# ESP8266_MySensorsGateway_v1_3.net
KiCad netlist of a schematic drawn in EAGLE
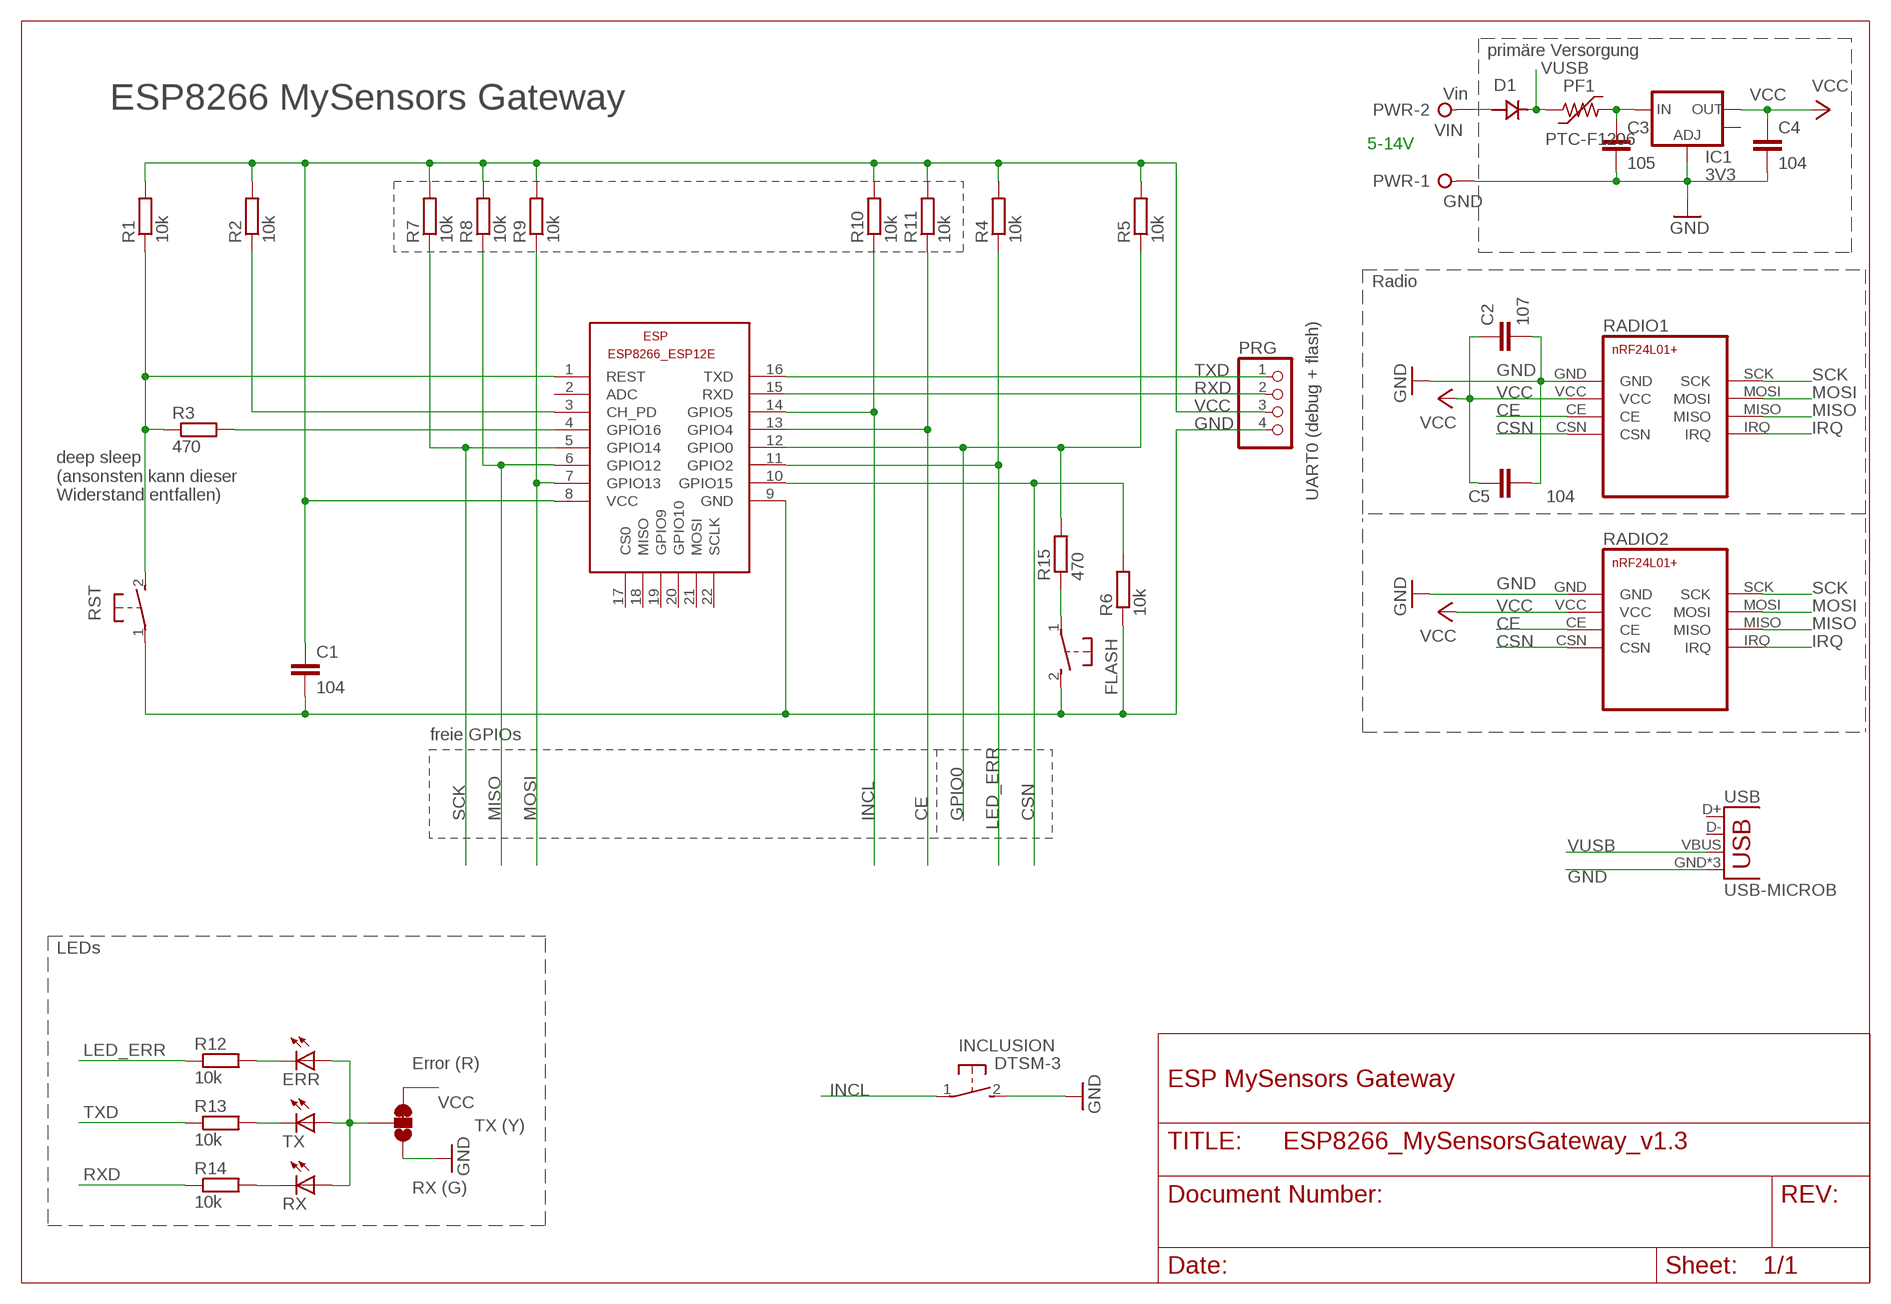
[diagram p0: schematic, sheet 1]

(export (version "E")
  (design (tool "Eeschema 10.0.6"))
  (components
    (comp (ref "C1")
      (value "104")
      (footprint "eagle-import:C0805")
      (libsource (lib "eagle-import") (part "C-EUC0805"))
    )
    (comp (ref "C2")
      (value "107")
      (footprint "eagle-import:MY1210")
      (libsource (lib "eagle-import") (part "C"))
    )
    (comp (ref "C3")
      (value "105")
      (footprint "eagle-import:C0805")
      (libsource (lib "eagle-import") (part "C-EUC0805"))
    )
    (comp (ref "C4")
      (value "104")
      (footprint "eagle-import:C0805")
      (libsource (lib "eagle-import") (part "C-EUC0805"))
    )
    (comp (ref "C5")
      (value "104")
      (footprint "eagle-import:C0805")
      (libsource (lib "eagle-import") (part "C-EUC0805"))
    )
    (comp (ref "D1")
      (value "SS14")
      (footprint "eagle-import:DO214")
      (libsource (lib "eagle-import") (part "SS14"))
    )
    (comp (ref "ERR")
      (value "R")
      (footprint "eagle-import:CHIPLED_1206")
      (libsource (lib "eagle-import") (part "LEDCHIPLED_1206"))
    )
    (comp (ref "ESP")
      (value "µC")
      (footprint "eagle-import:ESP8266-ESP12E")
      (libsource (lib "eagle-import") (part "ESP8266-12EESP8266-ESP12E"))
    )
    (comp (ref "FLASH")
      (value "DTSM-3")
      (footprint "eagle-import:DTSM-3")
      (libsource (lib "eagle-import") (part "DTSM-3"))
    )
    (comp (ref "IC1")
      (value "3V3")
      (footprint "eagle-import:SOT223")
      (libsource (lib "eagle-import") (part "V_REG_LM1117SOT223"))
    )
    (comp (ref "INCLUSION")
      (value "DTSM-3")
      (footprint "eagle-import:DTSM-3")
      (libsource (lib "eagle-import") (part "DTSM-3"))
    )
    (comp (ref "PF1")
      (value "PTC-F1206")
      (footprint "eagle-import:F1206")
      (libsource (lib "eagle-import") (part "PTC-F1206"))
    )
    (comp (ref "PRG")
      (value "PINHD-1X4_S")
      (footprint "eagle-import:1X04")
      (libsource (lib "eagle-import") (part "PINHD-1X4_S"))
    )
    (comp (ref "PWR")
      (value "Vin")
      (footprint "eagle-import:W237-132")
      (libsource (lib "eagle-import") (part "W237-02P"))
    )
    (comp (ref "R1")
      (value "10k")
      (footprint "eagle-import:R0805")
      (libsource (lib "eagle-import") (part "resistor_R-EU_R0805"))
    )
    (comp (ref "R2")
      (value "10k")
      (footprint "eagle-import:R0805")
      (libsource (lib "eagle-import") (part "resistor_R-EU_R0805"))
    )
    (comp (ref "R3")
      (value "470")
      (footprint "eagle-import:R0805")
      (libsource (lib "eagle-import") (part "resistor_R-EU_R0805"))
    )
    (comp (ref "R4")
      (value "10k")
      (footprint "eagle-import:R0805")
      (libsource (lib "eagle-import") (part "resistor_R-EU_R0805"))
    )
    (comp (ref "R5")
      (value "10k")
      (footprint "eagle-import:R0805")
      (libsource (lib "eagle-import") (part "resistor_R-EU_R0805"))
    )
    (comp (ref "R6")
      (value "10k")
      (footprint "eagle-import:R0805")
      (libsource (lib "eagle-import") (part "resistor_R-EU_R0805"))
    )
    (comp (ref "R7")
      (value "10k")
      (footprint "eagle-import:R0805")
      (libsource (lib "eagle-import") (part "resistor_R-EU_R0805"))
    )
    (comp (ref "R8")
      (value "10k")
      (footprint "eagle-import:R0805")
      (libsource (lib "eagle-import") (part "resistor_R-EU_R0805"))
    )
    (comp (ref "R9")
      (value "10k")
      (footprint "eagle-import:R0805")
      (libsource (lib "eagle-import") (part "resistor_R-EU_R0805"))
    )
    (comp (ref "R10")
      (value "10k")
      (footprint "eagle-import:R0805")
      (libsource (lib "eagle-import") (part "resistor_R-EU_R0805"))
    )
    (comp (ref "R11")
      (value "10k")
      (footprint "eagle-import:R0805")
      (libsource (lib "eagle-import") (part "resistor_R-EU_R0805"))
    )
    (comp (ref "R12")
      (value "10k")
      (footprint "eagle-import:R0805")
      (libsource (lib "eagle-import") (part "R-EU_R0805"))
    )
    (comp (ref "R13")
      (value "10k")
      (footprint "eagle-import:R0805")
      (libsource (lib "eagle-import") (part "R-EU_R0805"))
    )
    (comp (ref "R14")
      (value "10k")
      (footprint "eagle-import:R0805")
      (libsource (lib "eagle-import") (part "R-EU_R0805"))
    )
    (comp (ref "R15")
      (value "470")
      (footprint "eagle-import:R0805")
      (libsource (lib "eagle-import") (part "resistor_R-EU_R0805"))
    )
    (comp (ref "RADIO1")
      (value "NRF24L01+")
      (footprint "eagle-import:NRF24L01+")
      (libsource (lib "eagle-import") (part "NRF24L01+"))
    )
    (comp (ref "RADIO2")
      (value "NRF24L01+NRF24L01+MINI")
      (footprint "eagle-import:NRF24L01+MINI")
      (libsource (lib "eagle-import") (part "NRF24L01+NRF24L01+MINI"))
    )
    (comp (ref "RST")
      (value "DTSM-3")
      (footprint "eagle-import:DTSM-3")
      (libsource (lib "eagle-import") (part "DTSM-3"))
    )
    (comp (ref "RX")
      (value "G")
      (footprint "eagle-import:CHIPLED_1206")
      (libsource (lib "eagle-import") (part "LEDCHIPLED_1206"))
    )
    (comp (ref "SJ1")
      (value "JUMPER-PAD-3-2OF3_NC_BY_TRACE_SMALL")
      (footprint "eagle-import:PAD-JUMPER-3-2OF3_NC_BY_TRACE_YES_SILK_FULL_BOX")
      (libsource (lib "eagle-import") (part "JUMPER-PAD-3-2OF3_NC_BY_TRACE_SMALL"))
    )
    (comp (ref "TX")
      (value "Y")
      (footprint "eagle-import:CHIPLED_1206")
      (libsource (lib "eagle-import") (part "LEDCHIPLED_1206"))
    )
    (comp (ref "USB")
      (value "USB-MICROB")
      (footprint "eagle-import:USB-MICROB")
      (libsource (lib "eagle-import") (part "USB-MICROB"))
    )
  )
  (nets
    (net (code "1") (name "/CE") (class "Default")
      (node (ref "ESP") (pin "13") (pinfunction "GPIO4_13") (pintype "bidirectional"))
      (node (ref "R11") (pin "1") (pinfunction "1_1") (pintype "passive"))
      (node (ref "RADIO1") (pin "CE") (pinfunction "CE_CE") (pintype "bidirectional"))
      (node (ref "RADIO2") (pin "CE") (pinfunction "CE_CE") (pintype "bidirectional"))
    )
    (net (code "2") (name "/CSN") (class "Default")
      (node (ref "ESP") (pin "10") (pinfunction "GPIO15_10") (pintype "bidirectional"))
      (node (ref "R6") (pin "2") (pinfunction "2_2") (pintype "passive"))
      (node (ref "RADIO1") (pin "CSN") (pinfunction "CSN_CSN") (pintype "bidirectional"))
      (node (ref "RADIO2") (pin "CSN") (pinfunction "CSN_CSN") (pintype "bidirectional"))
    )
    (net (code "3") (name "/GPIO0") (class "Default")
      (node (ref "ESP") (pin "12") (pinfunction "GPIO0_12") (pintype "bidirectional"))
      (node (ref "R15") (pin "2") (pinfunction "2_2") (pintype "passive"))
      (node (ref "R5") (pin "1") (pinfunction "1_1") (pintype "passive"))
    )
    (net (code "4") (name "/INCL") (class "Default")
      (node (ref "ESP") (pin "14") (pinfunction "GPIO5_14") (pintype "bidirectional"))
      (node (ref "INCLUSION") (pin "1") (pinfunction "1_1") (pintype "passive"))
      (node (ref "R10") (pin "1") (pinfunction "1_1") (pintype "passive"))
    )
    (net (code "5") (name "/IRQ") (class "Default")
      (node (ref "RADIO1") (pin "IRQ") (pinfunction "IRQ_IRQ") (pintype "bidirectional"))
      (node (ref "RADIO2") (pin "IRQ") (pinfunction "IRQ_IRQ") (pintype "bidirectional"))
    )
    (net (code "6") (name "/LED_ERR") (class "Default")
      (node (ref "ESP") (pin "11") (pinfunction "GPIO2_11") (pintype "bidirectional"))
      (node (ref "R12") (pin "1") (pinfunction "1_1") (pintype "passive"))
      (node (ref "R4") (pin "1") (pinfunction "1_1") (pintype "passive"))
    )
    (net (code "7") (name "/MISO") (class "Default")
      (node (ref "ESP") (pin "6") (pinfunction "GPIO12_6") (pintype "bidirectional"))
      (node (ref "R8") (pin "1") (pinfunction "1_1") (pintype "passive"))
      (node (ref "RADIO1") (pin "MISO") (pinfunction "MISO_MISO") (pintype "bidirectional"))
      (node (ref "RADIO2") (pin "MISO") (pinfunction "MISO_MISO") (pintype "bidirectional"))
    )
    (net (code "8") (name "/MOSI") (class "Default")
      (node (ref "ESP") (pin "7") (pinfunction "GPIO13_7") (pintype "bidirectional"))
      (node (ref "R9") (pin "1") (pinfunction "1_1") (pintype "passive"))
      (node (ref "RADIO1") (pin "MOSI") (pinfunction "MOSI_MOSI") (pintype "bidirectional"))
      (node (ref "RADIO2") (pin "MOSI") (pinfunction "MOSI_MOSI") (pintype "bidirectional"))
    )
    (net (code "9") (name "/RXD") (class "Default")
      (node (ref "ESP") (pin "15") (pinfunction "RXD_15") (pintype "bidirectional"))
      (node (ref "PRG") (pin "2") (pinfunction "2_2") (pintype "passive"))
      (node (ref "R14") (pin "1") (pinfunction "1_1") (pintype "passive"))
    )
    (net (code "10") (name "/SCK") (class "Default")
      (node (ref "ESP") (pin "5") (pinfunction "GPIO14_5") (pintype "bidirectional"))
      (node (ref "R7") (pin "1") (pinfunction "1_1") (pintype "passive"))
      (node (ref "RADIO1") (pin "SCK") (pinfunction "SCK_SCK") (pintype "bidirectional"))
      (node (ref "RADIO2") (pin "SCK") (pinfunction "SCK_SCK") (pintype "bidirectional"))
    )
    (net (code "11") (name "/TXD") (class "Default")
      (node (ref "ESP") (pin "16") (pinfunction "TXD_16") (pintype "bidirectional"))
      (node (ref "PRG") (pin "1") (pinfunction "1_1") (pintype "passive"))
      (node (ref "R13") (pin "1") (pinfunction "1_1") (pintype "passive"))
    )
    (net (code "12") (name "/VIN") (class "Default")
      (node (ref "D1") (pin "ANODE") (pinfunction "ANODE_ANODE") (pintype "bidirectional"))
      (node (ref "PWR") (pin "2") (pinfunction "KL_2") (pintype "passive"))
    )
    (net (code "13") (name "/VUSB") (class "Default")
      (node (ref "D1") (pin "CATHODE") (pinfunction "CATHODE_CATHODE") (pintype "bidirectional"))
      (node (ref "PF1") (pin "1") (pinfunction "1_1") (pintype "passive"))
      (node (ref "USB") (pin "VBUS") (pinfunction "VBUS_VBUS") (pintype "bidirectional"))
    )
    (net (code "14") (name "GND") (class "Default")
      (node (ref "C1") (pin "2") (pinfunction "2_2") (pintype "passive"))
      (node (ref "C2") (pin "2") (pinfunction "2_2") (pintype "passive"))
      (node (ref "C3") (pin "2") (pinfunction "2_2") (pintype "passive"))
      (node (ref "C4") (pin "2") (pinfunction "2_2") (pintype "passive"))
      (node (ref "C5") (pin "2") (pinfunction "2_2") (pintype "passive"))
      (node (ref "ESP") (pin "9") (pinfunction "GND_9") (pintype "bidirectional"))
      (node (ref "FLASH") (pin "2") (pinfunction "2_2") (pintype "passive"))
      (node (ref "IC1") (pin "1") (pinfunction "ADJ_1") (pintype "input"))
      (node (ref "INCLUSION") (pin "2") (pinfunction "2_2") (pintype "passive"))
      (node (ref "PRG") (pin "4") (pinfunction "4_4") (pintype "passive"))
      (node (ref "PWR") (pin "1") (pinfunction "KL_1") (pintype "passive"))
      (node (ref "R6") (pin "1") (pinfunction "1_1") (pintype "passive"))
      (node (ref "RADIO1") (pin "GND") (pinfunction "GND_GND") (pintype "power_in"))
      (node (ref "RADIO2") (pin "GND") (pinfunction "GND_GND") (pintype "power_in"))
      (node (ref "RST") (pin "1") (pinfunction "1_1") (pintype "passive"))
      (node (ref "SJ1") (pin "1") (pinfunction "1_1") (pintype "passive"))
      (node (ref "USB") (pin "GND") (pinfunction "GND_GND") (pintype "bidirectional"))
      (node (ref "USB") (pin "MT1") (pinfunction "GND_MT1") (pintype "bidirectional"))
      (node (ref "USB") (pin "MT2") (pinfunction "GND_MT2") (pintype "bidirectional"))
    )
    (net (code "15") (name "Net-(ERR-PadA)") (class "Default")
      (node (ref "ERR") (pin "A") (pinfunction "A_A") (pintype "passive"))
      (node (ref "RX") (pin "A") (pinfunction "A_A") (pintype "passive"))
      (node (ref "SJ1") (pin "2") (pinfunction "2_2") (pintype "passive"))
      (node (ref "TX") (pin "A") (pinfunction "A_A") (pintype "passive"))
    )
    (net (code "16") (name "Net-(ERR-PadC)") (class "Default")
      (node (ref "ERR") (pin "C") (pinfunction "C_C") (pintype "passive"))
      (node (ref "R12") (pin "2") (pinfunction "2_2") (pintype "passive"))
    )
    (net (code "17") (name "Net-(ESP-CH_PD)") (class "Default")
      (node (ref "ESP") (pin "3") (pinfunction "CH_PD_3") (pintype "bidirectional"))
      (node (ref "R2") (pin "1") (pinfunction "1_1") (pintype "passive"))
    )
    (net (code "18") (name "Net-(ESP-GPIO16)") (class "Default")
      (node (ref "ESP") (pin "4") (pinfunction "GPIO16_4") (pintype "bidirectional"))
      (node (ref "R3") (pin "2") (pinfunction "2_2") (pintype "passive"))
    )
    (net (code "19") (name "Net-(ESP-REST)") (class "Default")
      (node (ref "ESP") (pin "1") (pinfunction "REST_1") (pintype "bidirectional"))
      (node (ref "R1") (pin "1") (pinfunction "1_1") (pintype "passive"))
      (node (ref "R3") (pin "1") (pinfunction "1_1") (pintype "passive"))
      (node (ref "RST") (pin "2") (pinfunction "2_2") (pintype "passive"))
    )
    (net (code "20") (name "Net-(FLASH-Pad1)") (class "Default")
      (node (ref "FLASH") (pin "1") (pinfunction "1_1") (pintype "passive"))
      (node (ref "R15") (pin "1") (pinfunction "1_1") (pintype "passive"))
    )
    (net (code "21") (name "Net-(IC1-IN)") (class "Default")
      (node (ref "C3") (pin "1") (pinfunction "1_1") (pintype "passive"))
      (node (ref "IC1") (pin "3") (pinfunction "IN_3") (pintype "input"))
      (node (ref "PF1") (pin "2") (pinfunction "2_2") (pintype "passive"))
    )
    (net (code "22") (name "Net-(R13-Pad2)") (class "Default")
      (node (ref "R13") (pin "2") (pinfunction "2_2") (pintype "passive"))
      (node (ref "TX") (pin "C") (pinfunction "C_C") (pintype "passive"))
    )
    (net (code "23") (name "Net-(R14-Pad2)") (class "Default")
      (node (ref "R14") (pin "2") (pinfunction "2_2") (pintype "passive"))
      (node (ref "RX") (pin "C") (pinfunction "C_C") (pintype "passive"))
    )
    (net (code "24") (name "VCC") (class "Default")
      (node (ref "C1") (pin "1") (pinfunction "1_1") (pintype "passive"))
      (node (ref "C2") (pin "1") (pinfunction "1_1") (pintype "passive"))
      (node (ref "C4") (pin "1") (pinfunction "1_1") (pintype "passive"))
      (node (ref "C5") (pin "1") (pinfunction "1_1") (pintype "passive"))
      (node (ref "ESP") (pin "8") (pinfunction "VCC_8") (pintype "bidirectional"))
      (node (ref "IC1") (pin "2") (pinfunction "OUT_2") (pintype "output"))
      (node (ref "PRG") (pin "3") (pinfunction "3_3") (pintype "passive"))
      (node (ref "R1") (pin "2") (pinfunction "2_2") (pintype "passive"))
      (node (ref "R10") (pin "2") (pinfunction "2_2") (pintype "passive"))
      (node (ref "R11") (pin "2") (pinfunction "2_2") (pintype "passive"))
      (node (ref "R2") (pin "2") (pinfunction "2_2") (pintype "passive"))
      (node (ref "R4") (pin "2") (pinfunction "2_2") (pintype "passive"))
      (node (ref "R5") (pin "2") (pinfunction "2_2") (pintype "passive"))
      (node (ref "R7") (pin "2") (pinfunction "2_2") (pintype "passive"))
      (node (ref "R8") (pin "2") (pinfunction "2_2") (pintype "passive"))
      (node (ref "R9") (pin "2") (pinfunction "2_2") (pintype "passive"))
      (node (ref "RADIO1") (pin "VCC") (pinfunction "VCC_VCC") (pintype "power_in"))
      (node (ref "RADIO2") (pin "VCC") (pinfunction "VCC_VCC") (pintype "power_in"))
      (node (ref "SJ1") (pin "3") (pinfunction "3_3") (pintype "passive"))
    )
    (net (code "25") (name "unconnected-(ESP-ADC-Pad2)") (class "Default")
      (node (ref "ESP") (pin "2") (pinfunction "ADC_2") (pintype "bidirectional"))
    )
    (net (code "26") (name "unconnected-(ESP-CS0-Pad17)") (class "Default")
      (node (ref "ESP") (pin "17") (pinfunction "CS0_17") (pintype "bidirectional"))
    )
    (net (code "27") (name "unconnected-(ESP-GPIO9-Pad19)") (class "Default")
      (node (ref "ESP") (pin "19") (pinfunction "GPIO9_19") (pintype "bidirectional"))
    )
    (net (code "28") (name "unconnected-(ESP-GPIO10-Pad20)") (class "Default")
      (node (ref "ESP") (pin "20") (pinfunction "GPIO10_20") (pintype "bidirectional"))
    )
    (net (code "29") (name "unconnected-(ESP-MISO-Pad18)") (class "Default")
      (node (ref "ESP") (pin "18") (pinfunction "MISO_18") (pintype "bidirectional"))
    )
    (net (code "30") (name "unconnected-(ESP-MOSI-Pad21)") (class "Default")
      (node (ref "ESP") (pin "21") (pinfunction "MOSI_21") (pintype "bidirectional"))
    )
    (net (code "31") (name "unconnected-(ESP-SCLK-Pad22)") (class "Default")
      (node (ref "ESP") (pin "22") (pinfunction "SCLK_22") (pintype "bidirectional"))
    )
    (net (code "32") (name "unconnected-(IC1-OUT-Pad4)") (class "Default")
      (node (ref "IC1") (pin "4") (pinfunction "OUT_4") (pintype "output"))
    )
    (net (code "33") (name "unconnected-(USB-PadD+)") (class "Default")
      (node (ref "USB") (pin "D+") (pinfunction "D+_D+") (pintype "bidirectional"))
    )
    (net (code "34") (name "unconnected-(USB-PadD-)") (class "Default")
      (node (ref "USB") (pin "D-") (pinfunction "D-_D-") (pintype "bidirectional"))
    )
  )
)
